# SCH_First_2024-01-22_1.net
KiCad netlist of a schematic drawn in EasyEDA
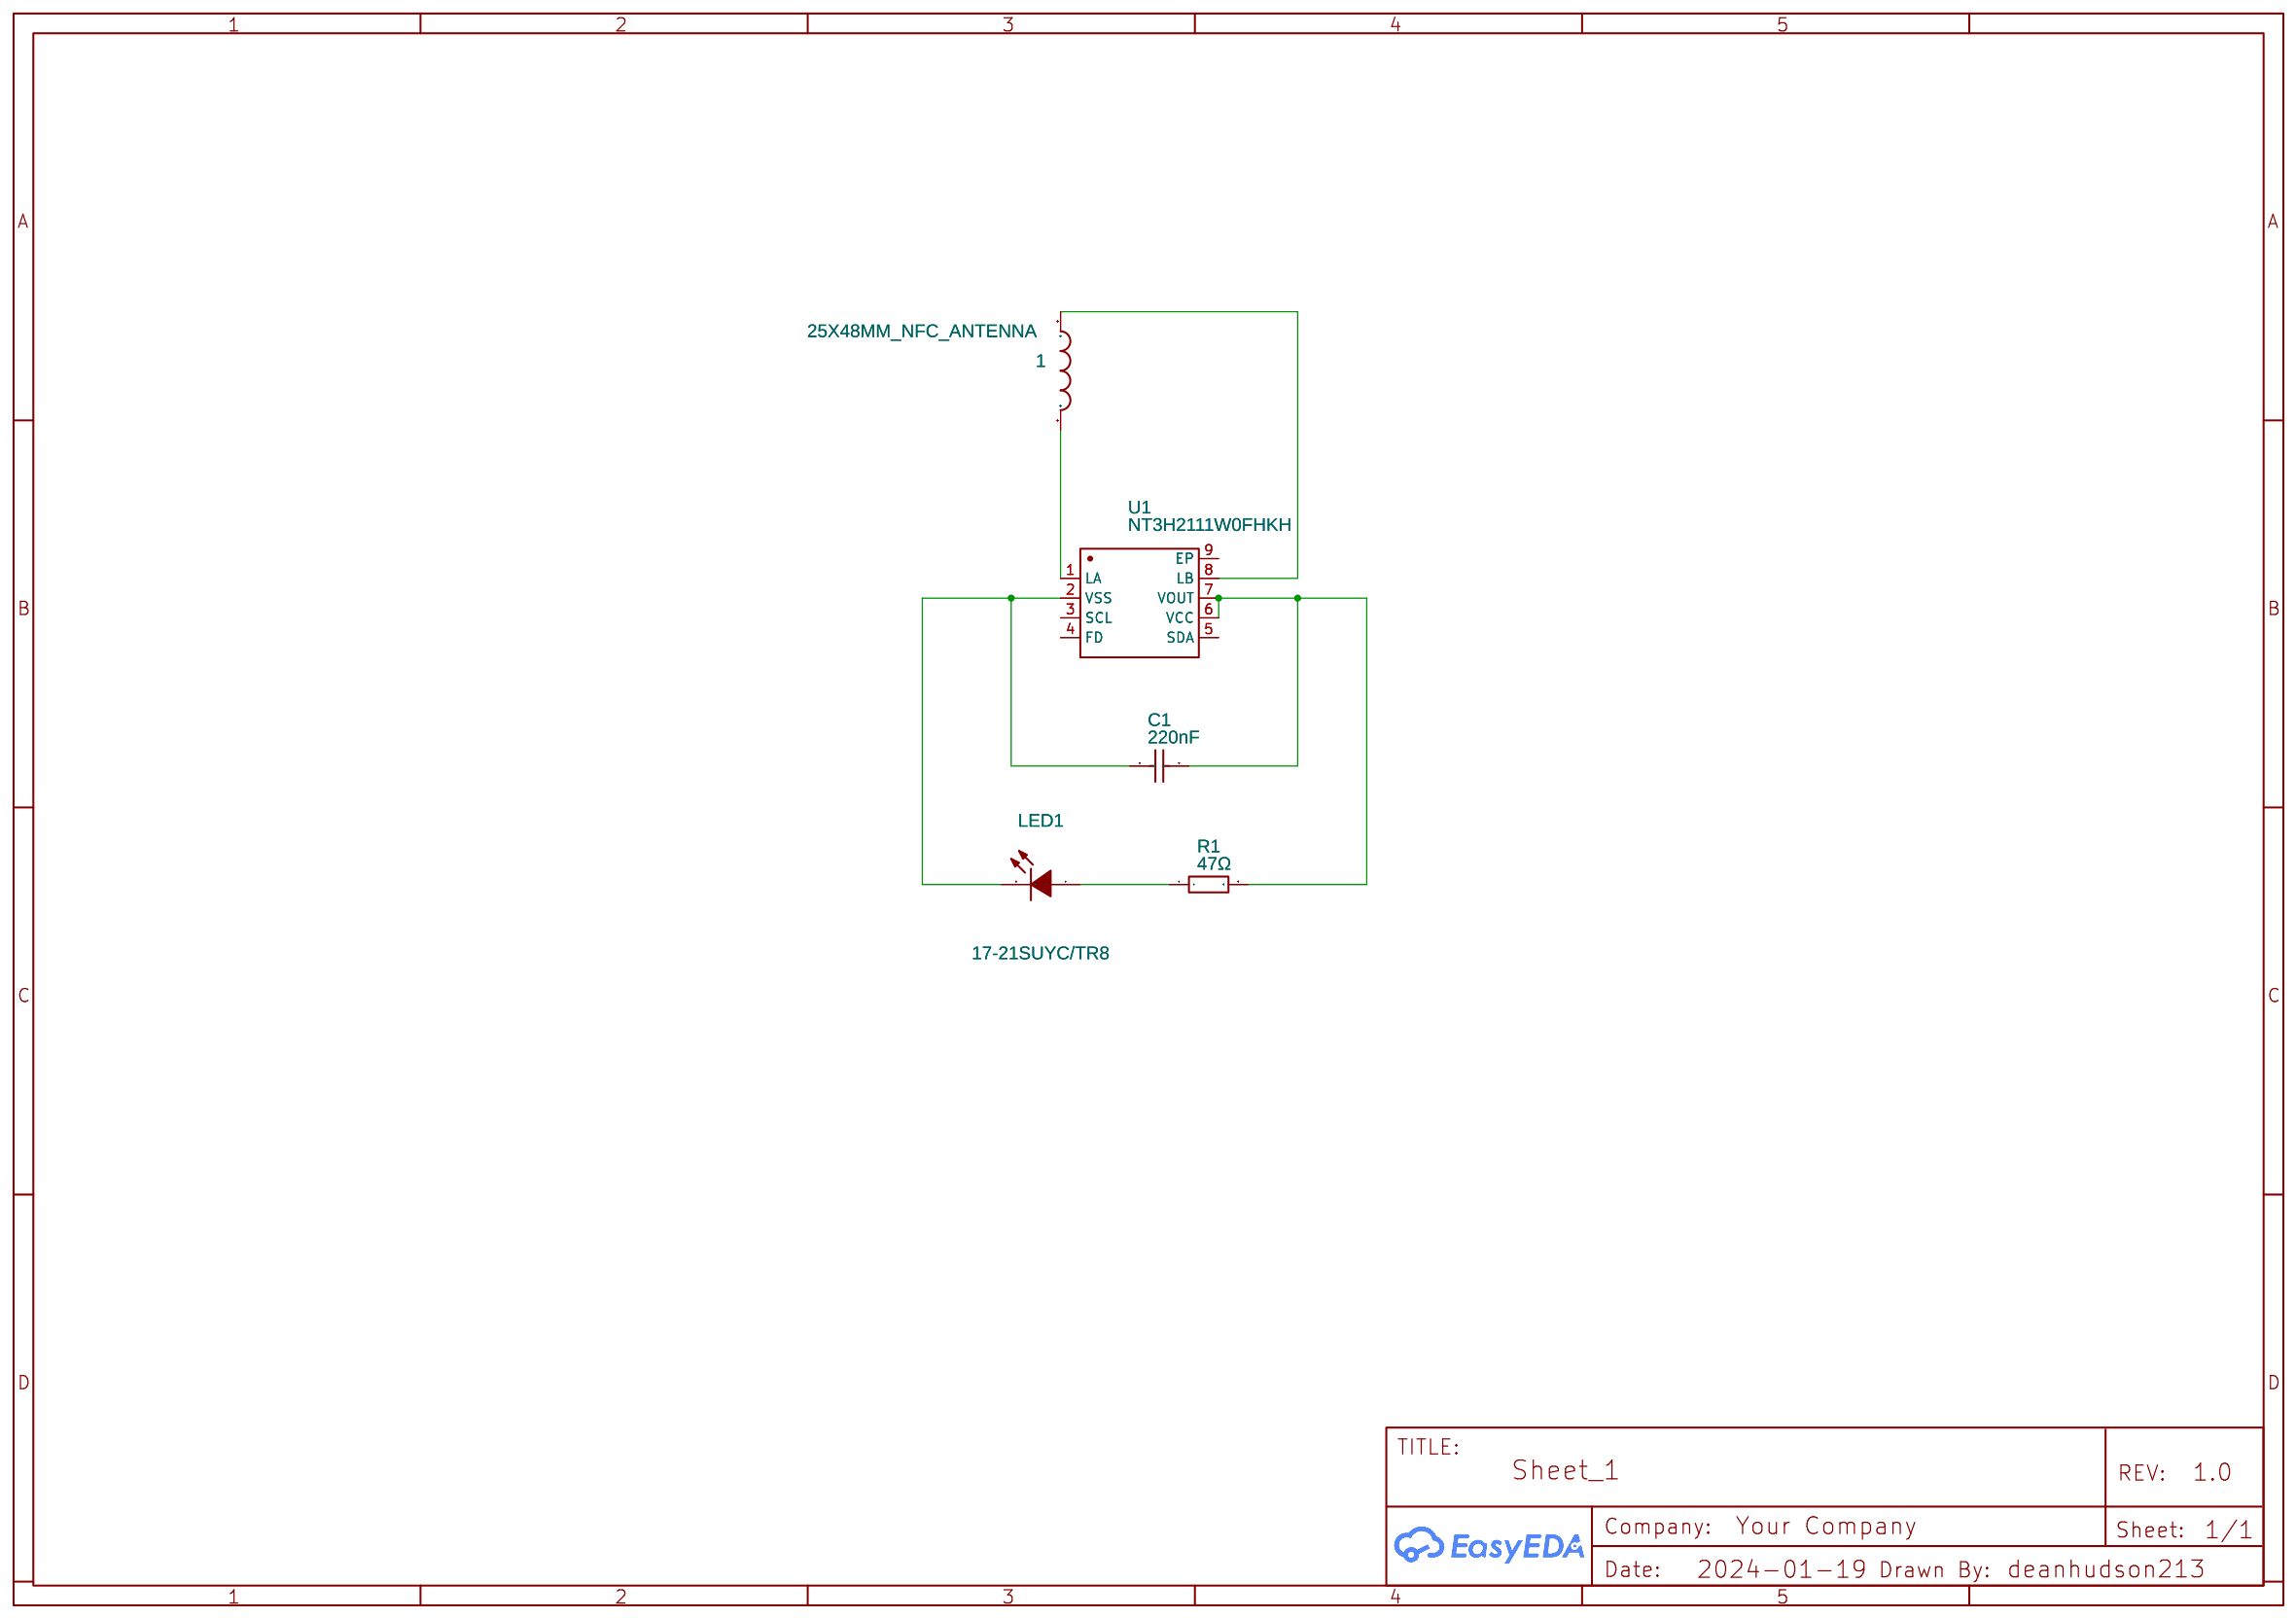
[diagram p0: schematic sheet]

(export (version "E")
  (design (tool "Eeschema 10.0.6"))
  (components
    (comp (ref "1") (value "25X48MM_NFC_ANTENNA") (libsource (lib "") (part "25X48MM_NFC_ANTENNA")))
    (comp (ref "C1")
      (value "220nF")
      (fields
        (field (name "Manufacturer Part") "CL10B224KA8NNNC")
        (field (name "Manufacturer") "SAMSUNG(三星)")
      )
      (libsource (lib "") (part "CL10B224KA8NNNC"))
    )
    (comp (ref "LED1")
      (value "17-21SUYC/TR8")
      (fields (field (name "Manufacturer Part") "KT-0805黄灯") (field (name "Manufacturer") "KENTO"))
      (libsource (lib "") (part "17-21SUYC/TR8"))
    )
    (comp (ref "R1")
      (value "47Ω")
      (fields
        (field (name "Manufacturer Part") "0603WAF470JT5E")
        (field (name "Manufacturer") "UNI-ROYAL(厚声)")
      )
      (libsource (lib "") (part "0603WAF470JT5E"))
    )
    (comp (ref "U1")
      (value "NT3H2111W0FHKH")
      (fields (field (name "Manufacturer") "NXP(恩智浦)"))
      (libsource (lib "") (part "NT3H2111W0FHKH"))
    )
  )
  (nets
    (net (code "1") (name "Net-(LED1-+)") (class "Default")
      (node (ref "LED1") (pin "1") (pinfunction "+_1") (pintype "unspecified"))
      (node (ref "R1") (pin "1") (pinfunction "1_1") (pintype "input"))
    )
    (net (code "2") (name "Net-(LED1--)") (class "Default")
      (node (ref "C1") (pin "1") (pinfunction "1_1") (pintype "input"))
      (node (ref "LED1") (pin "2") (pinfunction "-_2") (pintype "unspecified"))
      (node (ref "U1") (pin "2") (pinfunction "VSS_2") (pintype "unspecified"))
    )
    (net (code "3") (name "Net-(U1-LA)") (class "Default")
      (node (ref "1") (pin "P$2") (pinfunction "P$2_P$2") (pintype "bidirectional"))
      (node (ref "U1") (pin "1") (pinfunction "LA_1") (pintype "unspecified"))
    )
    (net (code "4") (name "Net-(U1-LB)") (class "Default")
      (node (ref "1") (pin "P$1") (pinfunction "P$1_P$1") (pintype "bidirectional"))
      (node (ref "U1") (pin "8") (pinfunction "LB_8") (pintype "unspecified"))
    )
    (net (code "5") (name "Net-(U1-VCC)") (class "Default")
      (node (ref "C1") (pin "2") (pinfunction "2_2") (pintype "input"))
      (node (ref "R1") (pin "2") (pinfunction "2_2") (pintype "input"))
      (node (ref "U1") (pin "6") (pinfunction "VCC_6") (pintype "unspecified"))
      (node (ref "U1") (pin "7") (pinfunction "VOUT_7") (pintype "unspecified"))
    )
    (net (code "6") (name "unconnected-(U1-EP-Pad9)") (class "Default")
      (node (ref "U1") (pin "9") (pinfunction "EP_9") (pintype "unspecified"))
    )
    (net (code "7") (name "unconnected-(U1-FD-Pad4)") (class "Default")
      (node (ref "U1") (pin "4") (pinfunction "FD_4") (pintype "unspecified"))
    )
    (net (code "8") (name "unconnected-(U1-SCL-Pad3)") (class "Default")
      (node (ref "U1") (pin "3") (pinfunction "SCL_3") (pintype "unspecified"))
    )
    (net (code "9") (name "unconnected-(U1-SDA-Pad5)") (class "Default")
      (node (ref "U1") (pin "5") (pinfunction "SDA_5") (pintype "unspecified"))
    )
  )
)
